# ASD2811.net
KiCad netlist of a schematic drawn in EAGLE
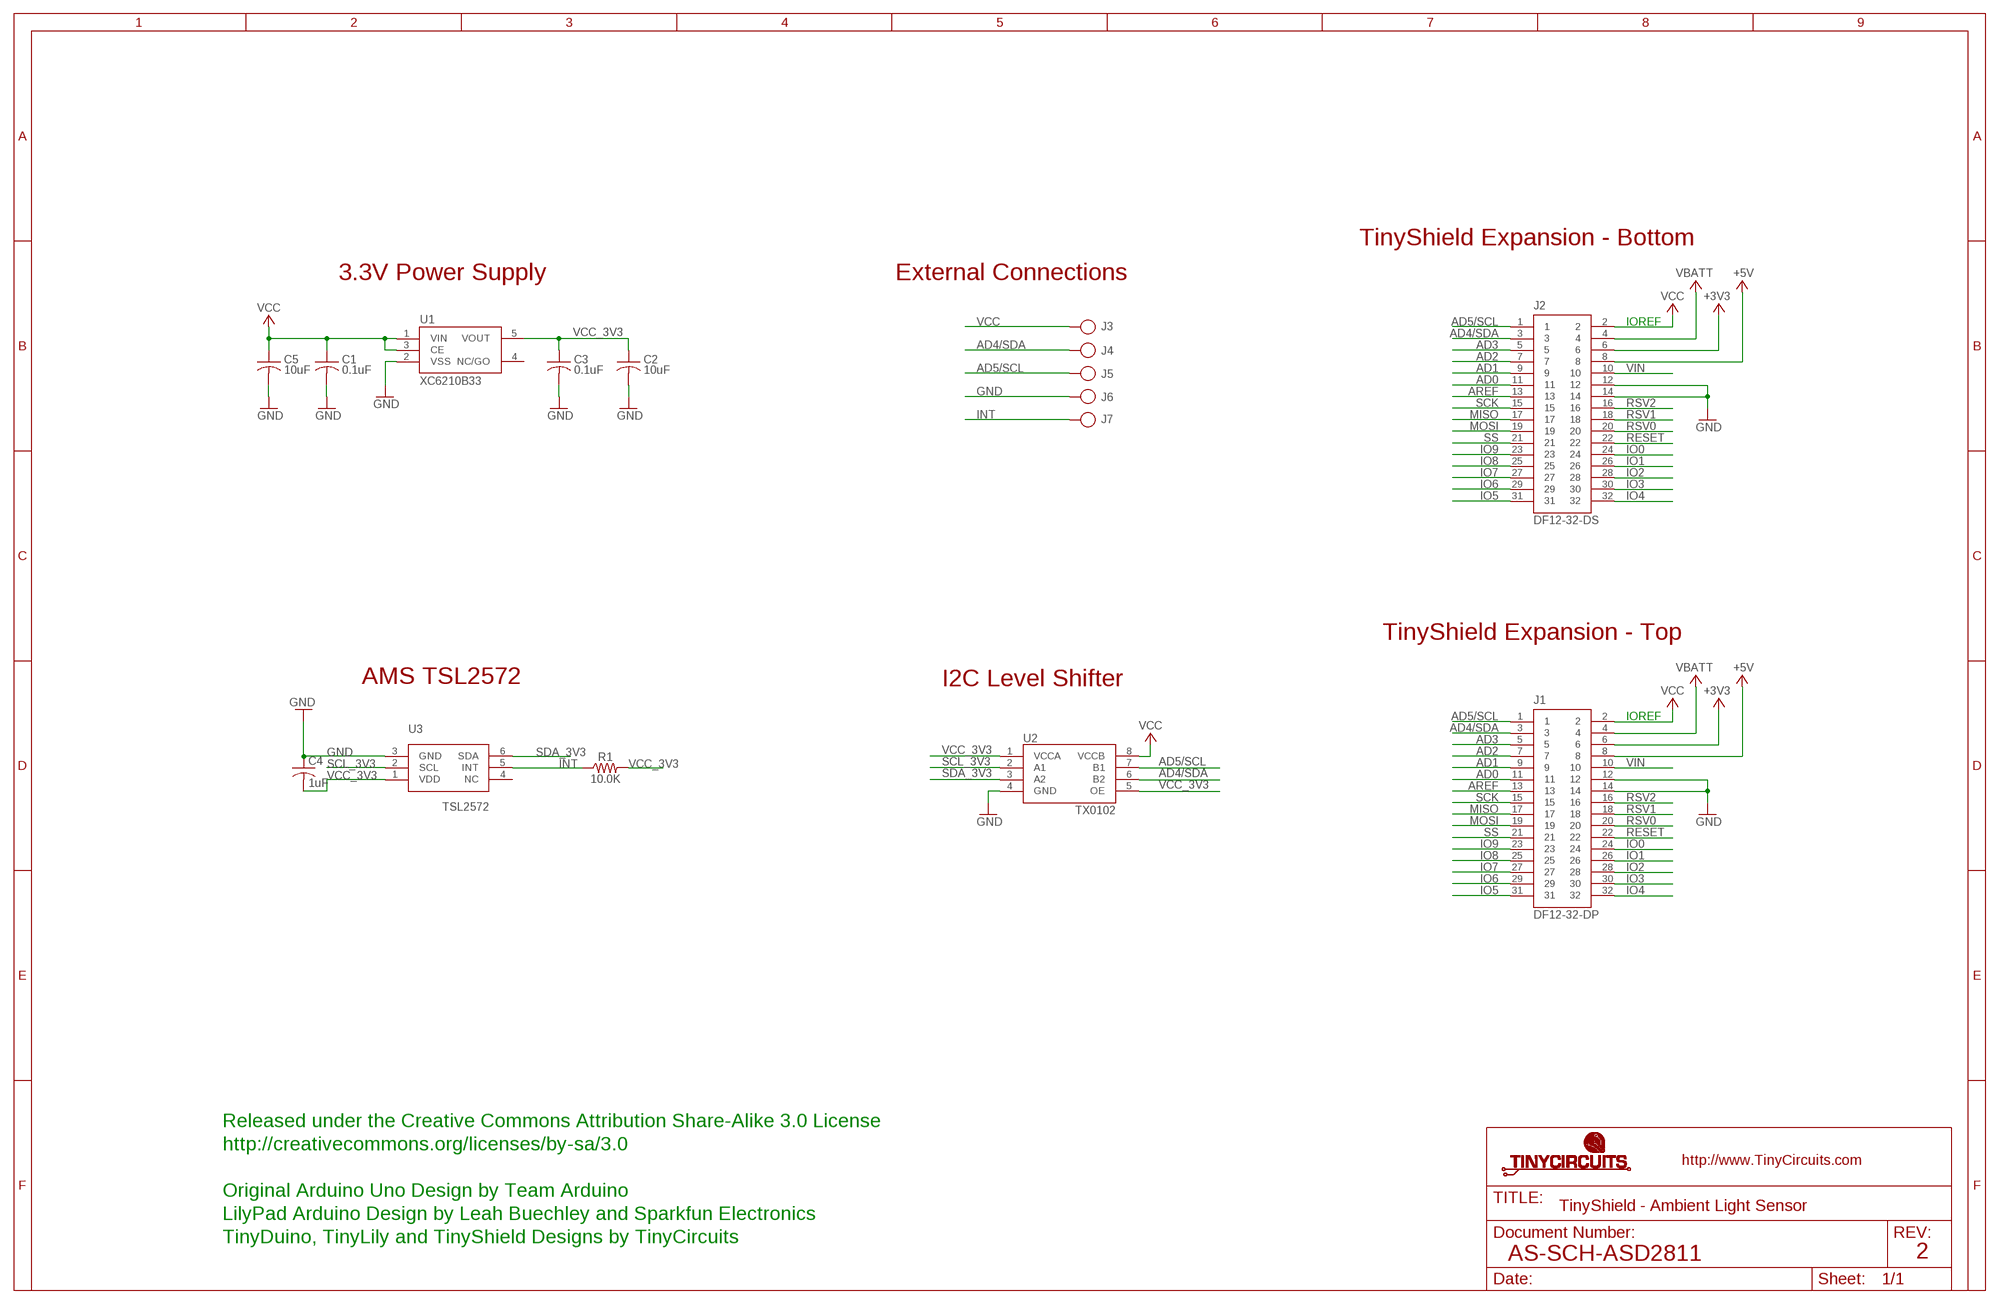
[diagram p0: schematic, sheet 1]

(export (version "E")
  (design (tool "Eeschema 10.0.6"))
  (components
    (comp (ref "C1")
      (value "0.1uF")
      (footprint "eagle-import:C0402")
      (fields (field (name "PARTNO") "AS-ITM-00008") (field (name "PARTNO_1") "AS-ITM-00008"))
      (libsource (lib "eagle-import") (part "AS-ITM-00008"))
    )
    (comp (ref "C2")
      (value "10uF")
      (footprint "eagle-import:C0805")
      (fields (field (name "PARTNO") "AS-ITM-00045") (field (name "PARTNO_1") "AS-ITM-00045"))
      (libsource (lib "eagle-import") (part "AS-ITM-00045"))
    )
    (comp (ref "C3")
      (value "0.1uF")
      (footprint "eagle-import:C0402")
      (fields (field (name "PARTNO") "AS-ITM-00008") (field (name "PARTNO_1") "AS-ITM-00008"))
      (libsource (lib "eagle-import") (part "AS-ITM-00008"))
    )
    (comp (ref "C4")
      (value "1uF")
      (footprint "eagle-import:C0402")
      (fields (field (name "PARTNO") "AS-ITM-00105"))
      (libsource (lib "eagle-import") (part "AS-ITM-00105"))
    )
    (comp (ref "C5")
      (value "10uF")
      (footprint "eagle-import:C0805")
      (fields (field (name "PARTNO") "AS-ITM-00045"))
      (libsource (lib "eagle-import") (part "AS-ITM-00045"))
    )
    (comp (ref "J1")
      (value "DF12-32-DP")
      (footprint "eagle-import:DF12-32-DP")
      (fields (field (name "PARTNO") "AS-ITM-00015") (field (name "PARTNO_1") "AS-ITM-00015"))
      (libsource (lib "eagle-import") (part "AS-ITM-00015"))
    )
    (comp (ref "J2")
      (value "DF12-32-DS")
      (footprint "eagle-import:DF12-32-DS")
      (fields (field (name "PARTNO") "AS-ITM-00012") (field (name "PARTNO_1") "AS-ITM-00012"))
      (libsource (lib "eagle-import") (part "AS-ITM-00012"))
    )
    (comp (ref "J3")
      (value "PIN_1X.1\"")
      (footprint "eagle-import:1X.1_")
      (libsource (lib "eagle-import") (part "PIN_1X.1{dblquote}"))
    )
    (comp (ref "J4")
      (value "PIN_1X.1\"")
      (footprint "eagle-import:1X.1_")
      (libsource (lib "eagle-import") (part "PIN_1X.1{dblquote}"))
    )
    (comp (ref "J5")
      (value "PIN_1X.1\"")
      (footprint "eagle-import:1X.1_")
      (libsource (lib "eagle-import") (part "PIN_1X.1{dblquote}"))
    )
    (comp (ref "J6")
      (value "PIN_1X.1\"")
      (footprint "eagle-import:1X.1_")
      (libsource (lib "eagle-import") (part "PIN_1X.1{dblquote}"))
    )
    (comp (ref "J7")
      (value "PIN_1X.1\"")
      (footprint "eagle-import:1X.1_")
      (libsource (lib "eagle-import") (part "PIN_1X.1{dblquote}"))
    )
    (comp (ref "R1")
      (value "10.0K")
      (footprint "eagle-import:0402")
      (fields (field (name "PARTNO") "AS-ITM-00032"))
      (libsource (lib "eagle-import") (part "AS-ITM-00032"))
    )
    (comp (ref "U1")
      (value "XC6210B33")
      (footprint "eagle-import:SOT-25")
      (fields (field (name "PARTNO") "AS-ITM-00046"))
      (libsource (lib "eagle-import") (part "AS-ITM-00046"))
    )
    (comp (ref "U2")
      (value "TX0102")
      (footprint "eagle-import:DQE(R-PX2SON-N8)")
      (fields (field (name "PARTNO") "AS-ITM-00073"))
      (libsource (lib "eagle-import") (part "AS-ITM-00073"))
    )
    (comp (ref "U3")
      (value "TSL2572")
      (footprint "eagle-import:TSL2572")
      (fields (field (name "PARTNO") "AS-ITM-00116"))
      (libsource (lib "eagle-import") (part "AS-ITM-00116"))
    )
  )
  (nets
    (net (code "1") (name "+3V3") (class "Default")
      (node (ref "J1") (pin "6") (pinfunction "6_6") (pintype "bidirectional"))
      (node (ref "J2") (pin "6") (pinfunction "6_6") (pintype "bidirectional"))
    )
    (net (code "2") (name "+5V") (class "Default")
      (node (ref "J1") (pin "8") (pinfunction "8_8") (pintype "bidirectional"))
      (node (ref "J2") (pin "8") (pinfunction "8_8") (pintype "bidirectional"))
    )
    (net (code "3") (name "/AD0") (class "Default")
      (node (ref "J1") (pin "11") (pinfunction "11_11") (pintype "bidirectional"))
      (node (ref "J2") (pin "11") (pinfunction "11_11") (pintype "bidirectional"))
    )
    (net (code "4") (name "/AD1") (class "Default")
      (node (ref "J1") (pin "9") (pinfunction "9_9") (pintype "bidirectional"))
      (node (ref "J2") (pin "9") (pinfunction "9_9") (pintype "bidirectional"))
    )
    (net (code "5") (name "/AD2") (class "Default")
      (node (ref "J1") (pin "7") (pinfunction "7_7") (pintype "bidirectional"))
      (node (ref "J2") (pin "7") (pinfunction "7_7") (pintype "bidirectional"))
    )
    (net (code "6") (name "/AD3") (class "Default")
      (node (ref "J1") (pin "5") (pinfunction "5_5") (pintype "bidirectional"))
      (node (ref "J2") (pin "5") (pinfunction "5_5") (pintype "bidirectional"))
    )
    (net (code "7") (name "/AD4{slash}SDA") (class "Default")
      (node (ref "J1") (pin "3") (pinfunction "3_3") (pintype "bidirectional"))
      (node (ref "J2") (pin "3") (pinfunction "3_3") (pintype "bidirectional"))
      (node (ref "J4") (pin "1") (pinfunction "1_1") (pintype "bidirectional"))
      (node (ref "U2") (pin "6") (pinfunction "B2_6") (pintype "bidirectional"))
    )
    (net (code "8") (name "/AD5{slash}SCL") (class "Default")
      (node (ref "J1") (pin "1") (pinfunction "1_1") (pintype "bidirectional"))
      (node (ref "J2") (pin "1") (pinfunction "1_1") (pintype "bidirectional"))
      (node (ref "J5") (pin "1") (pinfunction "1_1") (pintype "bidirectional"))
      (node (ref "U2") (pin "7") (pinfunction "B1_7") (pintype "bidirectional"))
    )
    (net (code "9") (name "/AREF") (class "Default")
      (node (ref "J1") (pin "13") (pinfunction "13_13") (pintype "bidirectional"))
      (node (ref "J2") (pin "13") (pinfunction "13_13") (pintype "bidirectional"))
    )
    (net (code "10") (name "/INT") (class "Default")
      (node (ref "J7") (pin "1") (pinfunction "1_1") (pintype "bidirectional"))
      (node (ref "R1") (pin "1") (pinfunction "1_1") (pintype "passive"))
      (node (ref "U3") (pin "5") (pinfunction "INT_5") (pintype "bidirectional"))
    )
    (net (code "11") (name "/IO0") (class "Default")
      (node (ref "J1") (pin "24") (pinfunction "24_24") (pintype "bidirectional"))
      (node (ref "J2") (pin "24") (pinfunction "24_24") (pintype "bidirectional"))
    )
    (net (code "12") (name "/IO1") (class "Default")
      (node (ref "J1") (pin "26") (pinfunction "26_26") (pintype "bidirectional"))
      (node (ref "J2") (pin "26") (pinfunction "26_26") (pintype "bidirectional"))
    )
    (net (code "13") (name "/IO2") (class "Default")
      (node (ref "J1") (pin "28") (pinfunction "28_28") (pintype "bidirectional"))
      (node (ref "J2") (pin "28") (pinfunction "28_28") (pintype "bidirectional"))
    )
    (net (code "14") (name "/IO3") (class "Default")
      (node (ref "J1") (pin "30") (pinfunction "30_30") (pintype "bidirectional"))
      (node (ref "J2") (pin "30") (pinfunction "30_30") (pintype "bidirectional"))
    )
    (net (code "15") (name "/IO4") (class "Default")
      (node (ref "J1") (pin "32") (pinfunction "32_32") (pintype "bidirectional"))
      (node (ref "J2") (pin "32") (pinfunction "32_32") (pintype "bidirectional"))
    )
    (net (code "16") (name "/IO5") (class "Default")
      (node (ref "J1") (pin "31") (pinfunction "31_31") (pintype "bidirectional"))
      (node (ref "J2") (pin "31") (pinfunction "31_31") (pintype "bidirectional"))
    )
    (net (code "17") (name "/IO6") (class "Default")
      (node (ref "J1") (pin "29") (pinfunction "29_29") (pintype "bidirectional"))
      (node (ref "J2") (pin "29") (pinfunction "29_29") (pintype "bidirectional"))
    )
    (net (code "18") (name "/IO7") (class "Default")
      (node (ref "J1") (pin "27") (pinfunction "27_27") (pintype "bidirectional"))
      (node (ref "J2") (pin "27") (pinfunction "27_27") (pintype "bidirectional"))
    )
    (net (code "19") (name "/IO8") (class "Default")
      (node (ref "J1") (pin "25") (pinfunction "25_25") (pintype "bidirectional"))
      (node (ref "J2") (pin "25") (pinfunction "25_25") (pintype "bidirectional"))
    )
    (net (code "20") (name "/IO9") (class "Default")
      (node (ref "J1") (pin "23") (pinfunction "23_23") (pintype "bidirectional"))
      (node (ref "J2") (pin "23") (pinfunction "23_23") (pintype "bidirectional"))
    )
    (net (code "21") (name "/MISO") (class "Default")
      (node (ref "J1") (pin "17") (pinfunction "17_17") (pintype "bidirectional"))
      (node (ref "J2") (pin "17") (pinfunction "17_17") (pintype "bidirectional"))
    )
    (net (code "22") (name "/MOSI") (class "Default")
      (node (ref "J1") (pin "19") (pinfunction "19_19") (pintype "bidirectional"))
      (node (ref "J2") (pin "19") (pinfunction "19_19") (pintype "bidirectional"))
    )
    (net (code "23") (name "/RESET") (class "Default")
      (node (ref "J1") (pin "22") (pinfunction "22_22") (pintype "bidirectional"))
      (node (ref "J2") (pin "22") (pinfunction "22_22") (pintype "bidirectional"))
    )
    (net (code "24") (name "/RSV0") (class "Default")
      (node (ref "J1") (pin "20") (pinfunction "20_20") (pintype "bidirectional"))
      (node (ref "J2") (pin "20") (pinfunction "20_20") (pintype "bidirectional"))
    )
    (net (code "25") (name "/RSV1") (class "Default")
      (node (ref "J1") (pin "18") (pinfunction "18_18") (pintype "bidirectional"))
      (node (ref "J2") (pin "18") (pinfunction "18_18") (pintype "bidirectional"))
    )
    (net (code "26") (name "/RSV2") (class "Default")
      (node (ref "J1") (pin "16") (pinfunction "16_16") (pintype "bidirectional"))
      (node (ref "J2") (pin "16") (pinfunction "16_16") (pintype "bidirectional"))
    )
    (net (code "27") (name "/SCK") (class "Default")
      (node (ref "J1") (pin "15") (pinfunction "15_15") (pintype "bidirectional"))
      (node (ref "J2") (pin "15") (pinfunction "15_15") (pintype "bidirectional"))
    )
    (net (code "28") (name "/SCL_3V3") (class "Default")
      (node (ref "U2") (pin "2") (pinfunction "A1_2") (pintype "bidirectional"))
      (node (ref "U3") (pin "2") (pinfunction "SCL_2") (pintype "bidirectional"))
    )
    (net (code "29") (name "/SDA_3V3") (class "Default")
      (node (ref "U2") (pin "3") (pinfunction "A2_3") (pintype "bidirectional"))
      (node (ref "U3") (pin "6") (pinfunction "SDA_6") (pintype "bidirectional"))
    )
    (net (code "30") (name "/SS") (class "Default")
      (node (ref "J1") (pin "21") (pinfunction "21_21") (pintype "bidirectional"))
      (node (ref "J2") (pin "21") (pinfunction "21_21") (pintype "bidirectional"))
    )
    (net (code "31") (name "/VCC_3V3") (class "Default")
      (node (ref "C2") (pin "1") (pinfunction "1_1") (pintype "passive"))
      (node (ref "C3") (pin "1") (pinfunction "1_1") (pintype "passive"))
      (node (ref "C4") (pin "2") (pinfunction "2_2") (pintype "passive"))
      (node (ref "R1") (pin "2") (pinfunction "2_2") (pintype "passive"))
      (node (ref "U1") (pin "5") (pinfunction "VOUT_5") (pintype "bidirectional"))
      (node (ref "U2") (pin "1") (pinfunction "VCCA_1") (pintype "bidirectional"))
      (node (ref "U2") (pin "5") (pinfunction "OE_5") (pintype "bidirectional"))
      (node (ref "U3") (pin "1") (pinfunction "VDD_1") (pintype "bidirectional"))
    )
    (net (code "32") (name "/VIN") (class "Default")
      (node (ref "J1") (pin "10") (pinfunction "10_10") (pintype "bidirectional"))
      (node (ref "J2") (pin "10") (pinfunction "10_10") (pintype "bidirectional"))
    )
    (net (code "33") (name "GND") (class "Default")
      (node (ref "C1") (pin "2") (pinfunction "2_2") (pintype "passive"))
      (node (ref "C2") (pin "2") (pinfunction "2_2") (pintype "passive"))
      (node (ref "C3") (pin "2") (pinfunction "2_2") (pintype "passive"))
      (node (ref "C4") (pin "1") (pinfunction "1_1") (pintype "passive"))
      (node (ref "C5") (pin "2") (pinfunction "2_2") (pintype "passive"))
      (node (ref "J1") (pin "12") (pinfunction "12_12") (pintype "bidirectional"))
      (node (ref "J1") (pin "14") (pinfunction "14_14") (pintype "bidirectional"))
      (node (ref "J2") (pin "12") (pinfunction "12_12") (pintype "bidirectional"))
      (node (ref "J2") (pin "14") (pinfunction "14_14") (pintype "bidirectional"))
      (node (ref "J6") (pin "1") (pinfunction "1_1") (pintype "bidirectional"))
      (node (ref "U1") (pin "2") (pinfunction "VSS_2") (pintype "power_in"))
      (node (ref "U2") (pin "4") (pinfunction "GND_4") (pintype "bidirectional"))
      (node (ref "U3") (pin "3") (pinfunction "GND_3") (pintype "bidirectional"))
    )
    (net (code "34") (name "VBATT") (class "Default")
      (node (ref "J1") (pin "4") (pinfunction "4_4") (pintype "bidirectional"))
      (node (ref "J2") (pin "4") (pinfunction "4_4") (pintype "bidirectional"))
    )
    (net (code "35") (name "VCC") (class "Default")
      (node (ref "C1") (pin "1") (pinfunction "1_1") (pintype "passive"))
      (node (ref "C5") (pin "1") (pinfunction "1_1") (pintype "passive"))
      (node (ref "J1") (pin "2") (pinfunction "2_2") (pintype "bidirectional"))
      (node (ref "J2") (pin "2") (pinfunction "2_2") (pintype "bidirectional"))
      (node (ref "J3") (pin "1") (pinfunction "1_1") (pintype "bidirectional"))
      (node (ref "U1") (pin "1") (pinfunction "VIN_1") (pintype "bidirectional"))
      (node (ref "U1") (pin "3") (pinfunction "CE_3") (pintype "bidirectional"))
      (node (ref "U2") (pin "8") (pinfunction "VCCB_8") (pintype "bidirectional"))
    )
    (net (code "36") (name "unconnected-(U1-NC{slash}GO-Pad4)") (class "Default")
      (node (ref "U1") (pin "4") (pinfunction "NC/GO_4") (pintype "bidirectional"))
    )
    (net (code "37") (name "unconnected-(U3-NC-Pad4)") (class "Default")
      (node (ref "U3") (pin "4") (pinfunction "NC_4") (pintype "bidirectional"))
    )
  )
)
